# StyroCutter-556-heatsink-5V-alt.net
KiCad netlist of a schematic drawn in EAGLE
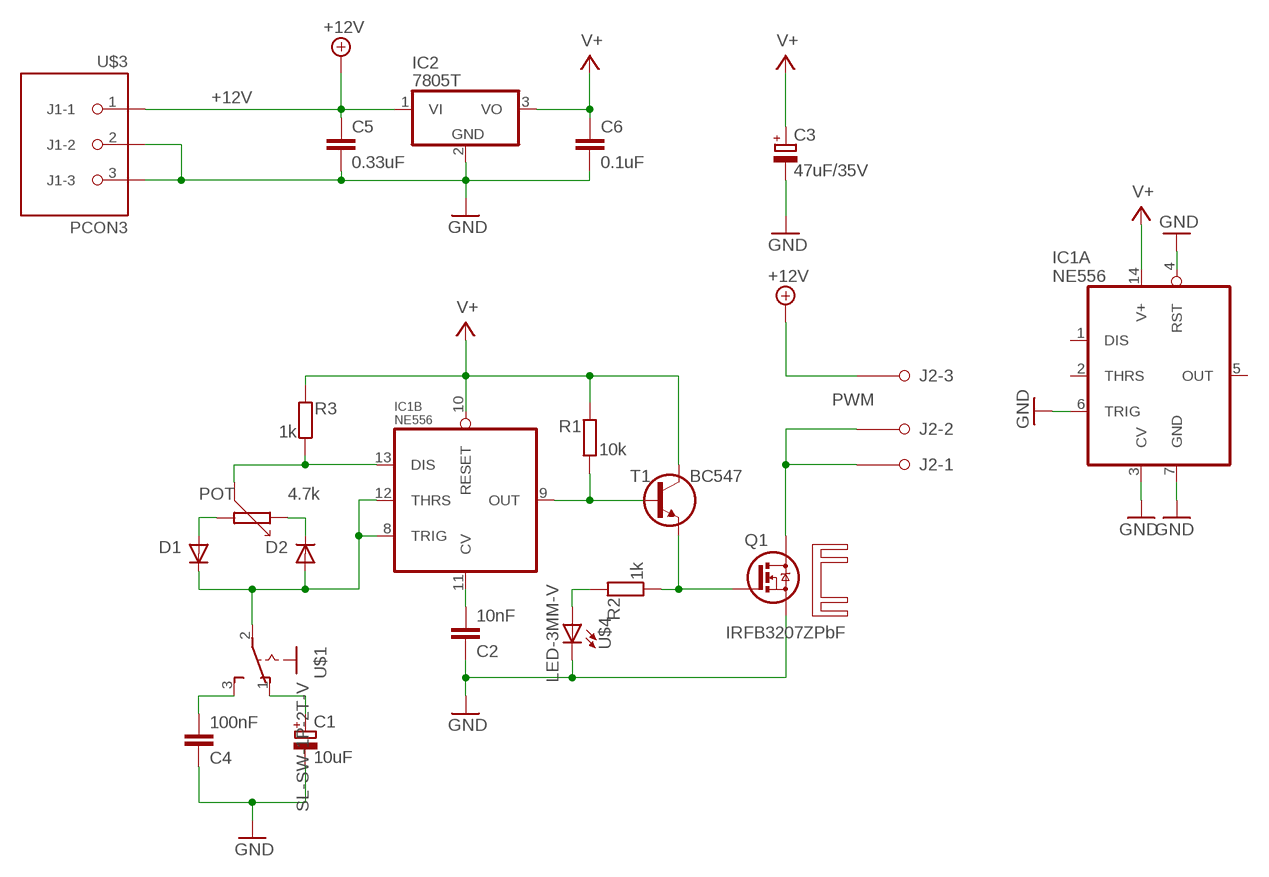
[diagram p0: schematic, sheet 1]

(export (version "E")
  (design (tool "Eeschema 10.0.6"))
  (components
    (comp (ref "C1")
      (value "10uF")
      (footprint "eagle-import:E5-4")
      (libsource (lib "eagle-import") (part "CPOL-EUE5-4"))
    )
    (comp (ref "C2")
      (value "10nF")
      (footprint "eagle-import:C075-032X103")
      (libsource (lib "eagle-import") (part "C075-032X103"))
    )
    (comp (ref "C3")
      (value "47uF/35V")
      (footprint "eagle-import:E2,5-5")
      (libsource (lib "eagle-import") (part "CPOL-EUE2.5-5"))
    )
    (comp (ref "C4")
      (value "100nF")
      (footprint "eagle-import:C050-020X036")
      (libsource (lib "eagle-import") (part "C050-020X036"))
    )
    (comp (ref "C5")
      (value "0.33uF")
      (footprint "eagle-import:C050-024X044")
      (libsource (lib "eagle-import") (part "C050-024X044"))
    )
    (comp (ref "C6")
      (value "0.1uF")
      (footprint "eagle-import:C050-025X075")
      (libsource (lib "eagle-import") (part "C050-025X075"))
    )
    (comp (ref "D1")
      (value "1N4148")
      (footprint "eagle-import:DO34-5")
      (libsource (lib "eagle-import") (part "1N414834-5"))
    )
    (comp (ref "D2")
      (value "1N4148")
      (footprint "eagle-import:DO34-5")
      (libsource (lib "eagle-import") (part "1N414834-5"))
    )
    (comp (ref "IC1")
      (value "NE556")
      (footprint "eagle-import:DIL14")
      (libsource (lib "eagle-import") (part "556-ALT-DIL14"))
    )
    (comp (ref "IC2")
      (value "7805T")
      (footprint "eagle-import:TO220H")
      (libsource (lib "eagle-import") (part "78T05"))
    )
    (comp (ref "J2")
      (value "PCON3_MIGROS")
      (footprint "eagle-import:CON-MIGROS-3PIN")
      (libsource (lib "eagle-import") (part "PCON3_MIGROS"))
    )
    (comp (ref "POT")
      (value "4.7k")
      (footprint "eagle-import:PC16S")
      (libsource (lib "eagle-import") (part "PIHER-PT16S"))
    )
    (comp (ref "Q1")
      (value "IRFB3207ZPbF")
      (footprint "eagle-import:TO220BV")
      (libsource (lib "eagle-import") (part "PMOSFET_NTO220BV"))
    )
    (comp (ref "R1")
      (value "10k")
      (footprint "eagle-import:0204_12")
      (libsource (lib "eagle-import") (part "R0204/12"))
    )
    (comp (ref "R2")
      (value "1k")
      (footprint "eagle-import:0204_10")
      (libsource (lib "eagle-import") (part "R0204/10"))
    )
    (comp (ref "R3")
      (value "1k")
      (footprint "eagle-import:0202_2V")
      (libsource (lib "eagle-import") (part "R0202/2V"))
    )
    (comp (ref "T1")
      (value "BC547")
      (footprint "eagle-import:TO92-CBE")
      (libsource (lib "eagle-import") (part "BC547CBE"))
    )
    (comp (ref "U$1")
      (value "SL-SW-1P-2T-V")
      (footprint "eagle-import:SLSW-1P2T-V")
      (libsource (lib "eagle-import") (part "SL-SW-1P-2T-V"))
    )
    (comp (ref "U$2")
      (value "AQ")
      (footprint "eagle-import:AQ_HS_3A")
      (libsource (lib "eagle-import") (part "AQ"))
    )
    (comp (ref "U$3")
      (value "PCON3")
      (footprint "eagle-import:CON-MIGROS-3PIN")
      (libsource (lib "eagle-import") (part "PCON3"))
    )
    (comp (ref "U$4")
      (value "LED-3MM-V")
      (footprint "eagle-import:LED-3MM-V")
      (libsource (lib "eagle-import") (part "LED-3MM-V"))
    )
  )
  (nets
    (net (code "1") (name "+12V") (class "Default")
      (node (ref "C5") (pin "1") (pinfunction "1_1") (pintype "passive"))
      (node (ref "IC2") (pin "1") (pinfunction "VI_1") (pintype "input"))
      (node (ref "J2") (pin "3") (pinfunction "1_3") (pintype "bidirectional"))
      (node (ref "U$3") (pin "1") (pinfunction "J1-1_1") (pintype "passive"))
    )
    (net (code "2") (name "/PWM") (class "Default")
      (node (ref "J2") (pin "1") (pinfunction "1_1") (pintype "bidirectional"))
      (node (ref "J2") (pin "2") (pinfunction "1_2") (pintype "bidirectional"))
      (node (ref "Q1") (pin "D") (pinfunction "D_D") (pintype "passive"))
    )
    (net (code "3") (name "GND") (class "Default")
      (node (ref "C1") (pin "-") (pinfunction "-_-") (pintype "passive"))
      (node (ref "C2") (pin "1") (pinfunction "1_1") (pintype "passive"))
      (node (ref "C3") (pin "-") (pinfunction "-_-") (pintype "passive"))
      (node (ref "C4") (pin "1") (pinfunction "1_1") (pintype "passive"))
      (node (ref "C5") (pin "2") (pinfunction "2_2") (pintype "passive"))
      (node (ref "C6") (pin "2") (pinfunction "2_2") (pintype "passive"))
      (node (ref "IC1") (pin "3") (pinfunction "CV_3") (pintype "input"))
      (node (ref "IC1") (pin "4") (pinfunction "RST_4") (pintype "input"))
      (node (ref "IC1") (pin "6") (pinfunction "TRIG_6") (pintype "input"))
      (node (ref "IC1") (pin "7") (pinfunction "GND_7") (pintype "power_in"))
      (node (ref "IC2") (pin "2") (pinfunction "GND_2") (pintype "passive"))
      (node (ref "Q1") (pin "S") (pinfunction "S_S") (pintype "passive"))
      (node (ref "U$3") (pin "2") (pinfunction "J1-2_2") (pintype "passive"))
      (node (ref "U$3") (pin "3") (pinfunction "J1-3_3") (pintype "passive"))
      (node (ref "U$4") (pin "C") (pinfunction "C_C") (pintype "passive"))
    )
    (net (code "4") (name "Net-(D1-PadA)") (class "Default")
      (node (ref "D1") (pin "A") (pinfunction "A_A") (pintype "passive"))
      (node (ref "POT") (pin "1E") (pinfunction "1E_1E") (pintype "passive"))
    )
    (net (code "5") (name "Net-(D2-PadC)") (class "Default")
      (node (ref "D2") (pin "C") (pinfunction "C_C") (pintype "passive"))
      (node (ref "POT") (pin "1A") (pinfunction "1A_1A") (pintype "passive"))
    )
    (net (code "6") (name "Net-(IC1B-CV)") (class "Default")
      (node (ref "C2") (pin "2") (pinfunction "2_2") (pintype "passive"))
      (node (ref "IC1") (pin "11") (pinfunction "CV_11") (pintype "input"))
    )
    (net (code "7") (name "Net-(IC1B-DIS)") (class "Default")
      (node (ref "IC1") (pin "13") (pinfunction "DIS_13") (pintype "input"))
      (node (ref "POT") (pin "1S") (pinfunction "1S_1S") (pintype "passive"))
      (node (ref "R3") (pin "1") (pinfunction "1_1") (pintype "passive"))
    )
    (net (code "8") (name "Net-(IC1B-OUT)") (class "Default")
      (node (ref "IC1") (pin "9") (pinfunction "OUT_9") (pintype "output"))
      (node (ref "R1") (pin "1") (pinfunction "1_1") (pintype "passive"))
      (node (ref "T1") (pin "B") (pinfunction "B_B") (pintype "passive"))
    )
    (net (code "9") (name "Net-(IC1B-THRS)") (class "Default")
      (node (ref "D1") (pin "C") (pinfunction "C_C") (pintype "passive"))
      (node (ref "D2") (pin "A") (pinfunction "A_A") (pintype "passive"))
      (node (ref "IC1") (pin "12") (pinfunction "THRS_12") (pintype "input"))
      (node (ref "IC1") (pin "8") (pinfunction "TRIG_8") (pintype "input"))
      (node (ref "U$1") (pin "2") (pinfunction "P_2") (pintype "passive"))
    )
    (net (code "10") (name "Net-(Q1-PadG)") (class "Default")
      (node (ref "Q1") (pin "G") (pinfunction "G_G") (pintype "passive"))
      (node (ref "R2") (pin "1") (pinfunction "1_1") (pintype "passive"))
      (node (ref "T1") (pin "E") (pinfunction "E_E") (pintype "passive"))
    )
    (net (code "11") (name "Net-(R2-Pad2)") (class "Default")
      (node (ref "R2") (pin "2") (pinfunction "2_2") (pintype "passive"))
      (node (ref "U$4") (pin "A") (pinfunction "A_A") (pintype "passive"))
    )
    (net (code "12") (name "Net-(U$1-O)") (class "Default")
      (node (ref "C1") (pin "+") (pinfunction "+_+") (pintype "passive"))
      (node (ref "U$1") (pin "1") (pinfunction "O_1") (pintype "passive"))
    )
    (net (code "13") (name "Net-(U$1-S)") (class "Default")
      (node (ref "C4") (pin "2") (pinfunction "2_2") (pintype "passive"))
      (node (ref "U$1") (pin "3") (pinfunction "S_3") (pintype "passive"))
    )
    (net (code "14") (name "V+") (class "Default")
      (node (ref "C3") (pin "+") (pinfunction "+_+") (pintype "passive"))
      (node (ref "C6") (pin "1") (pinfunction "1_1") (pintype "passive"))
      (node (ref "IC1") (pin "10") (pinfunction "RESET_10") (pintype "input"))
      (node (ref "IC1") (pin "14") (pinfunction "V+_14") (pintype "power_in"))
      (node (ref "IC2") (pin "3") (pinfunction "VO_3") (pintype "passive"))
      (node (ref "R1") (pin "2") (pinfunction "2_2") (pintype "passive"))
      (node (ref "R3") (pin "2") (pinfunction "2_2") (pintype "passive"))
      (node (ref "T1") (pin "C") (pinfunction "C_C") (pintype "passive"))
    )
    (net (code "15") (name "unconnected-(IC1A-DIS-Pad1)") (class "Default")
      (node (ref "IC1") (pin "1") (pinfunction "DIS_1") (pintype "input"))
    )
    (net (code "16") (name "unconnected-(IC1A-OUT-Pad5)") (class "Default")
      (node (ref "IC1") (pin "5") (pinfunction "OUT_5") (pintype "output"))
    )
    (net (code "17") (name "unconnected-(IC1A-THRS-Pad2)") (class "Default")
      (node (ref "IC1") (pin "2") (pinfunction "THRS_2") (pintype "input"))
    )
  )
)
